# SCH_Syntheseproject2_0_2022-10-21.net
KiCad netlist of a schematic drawn in EasyEDA
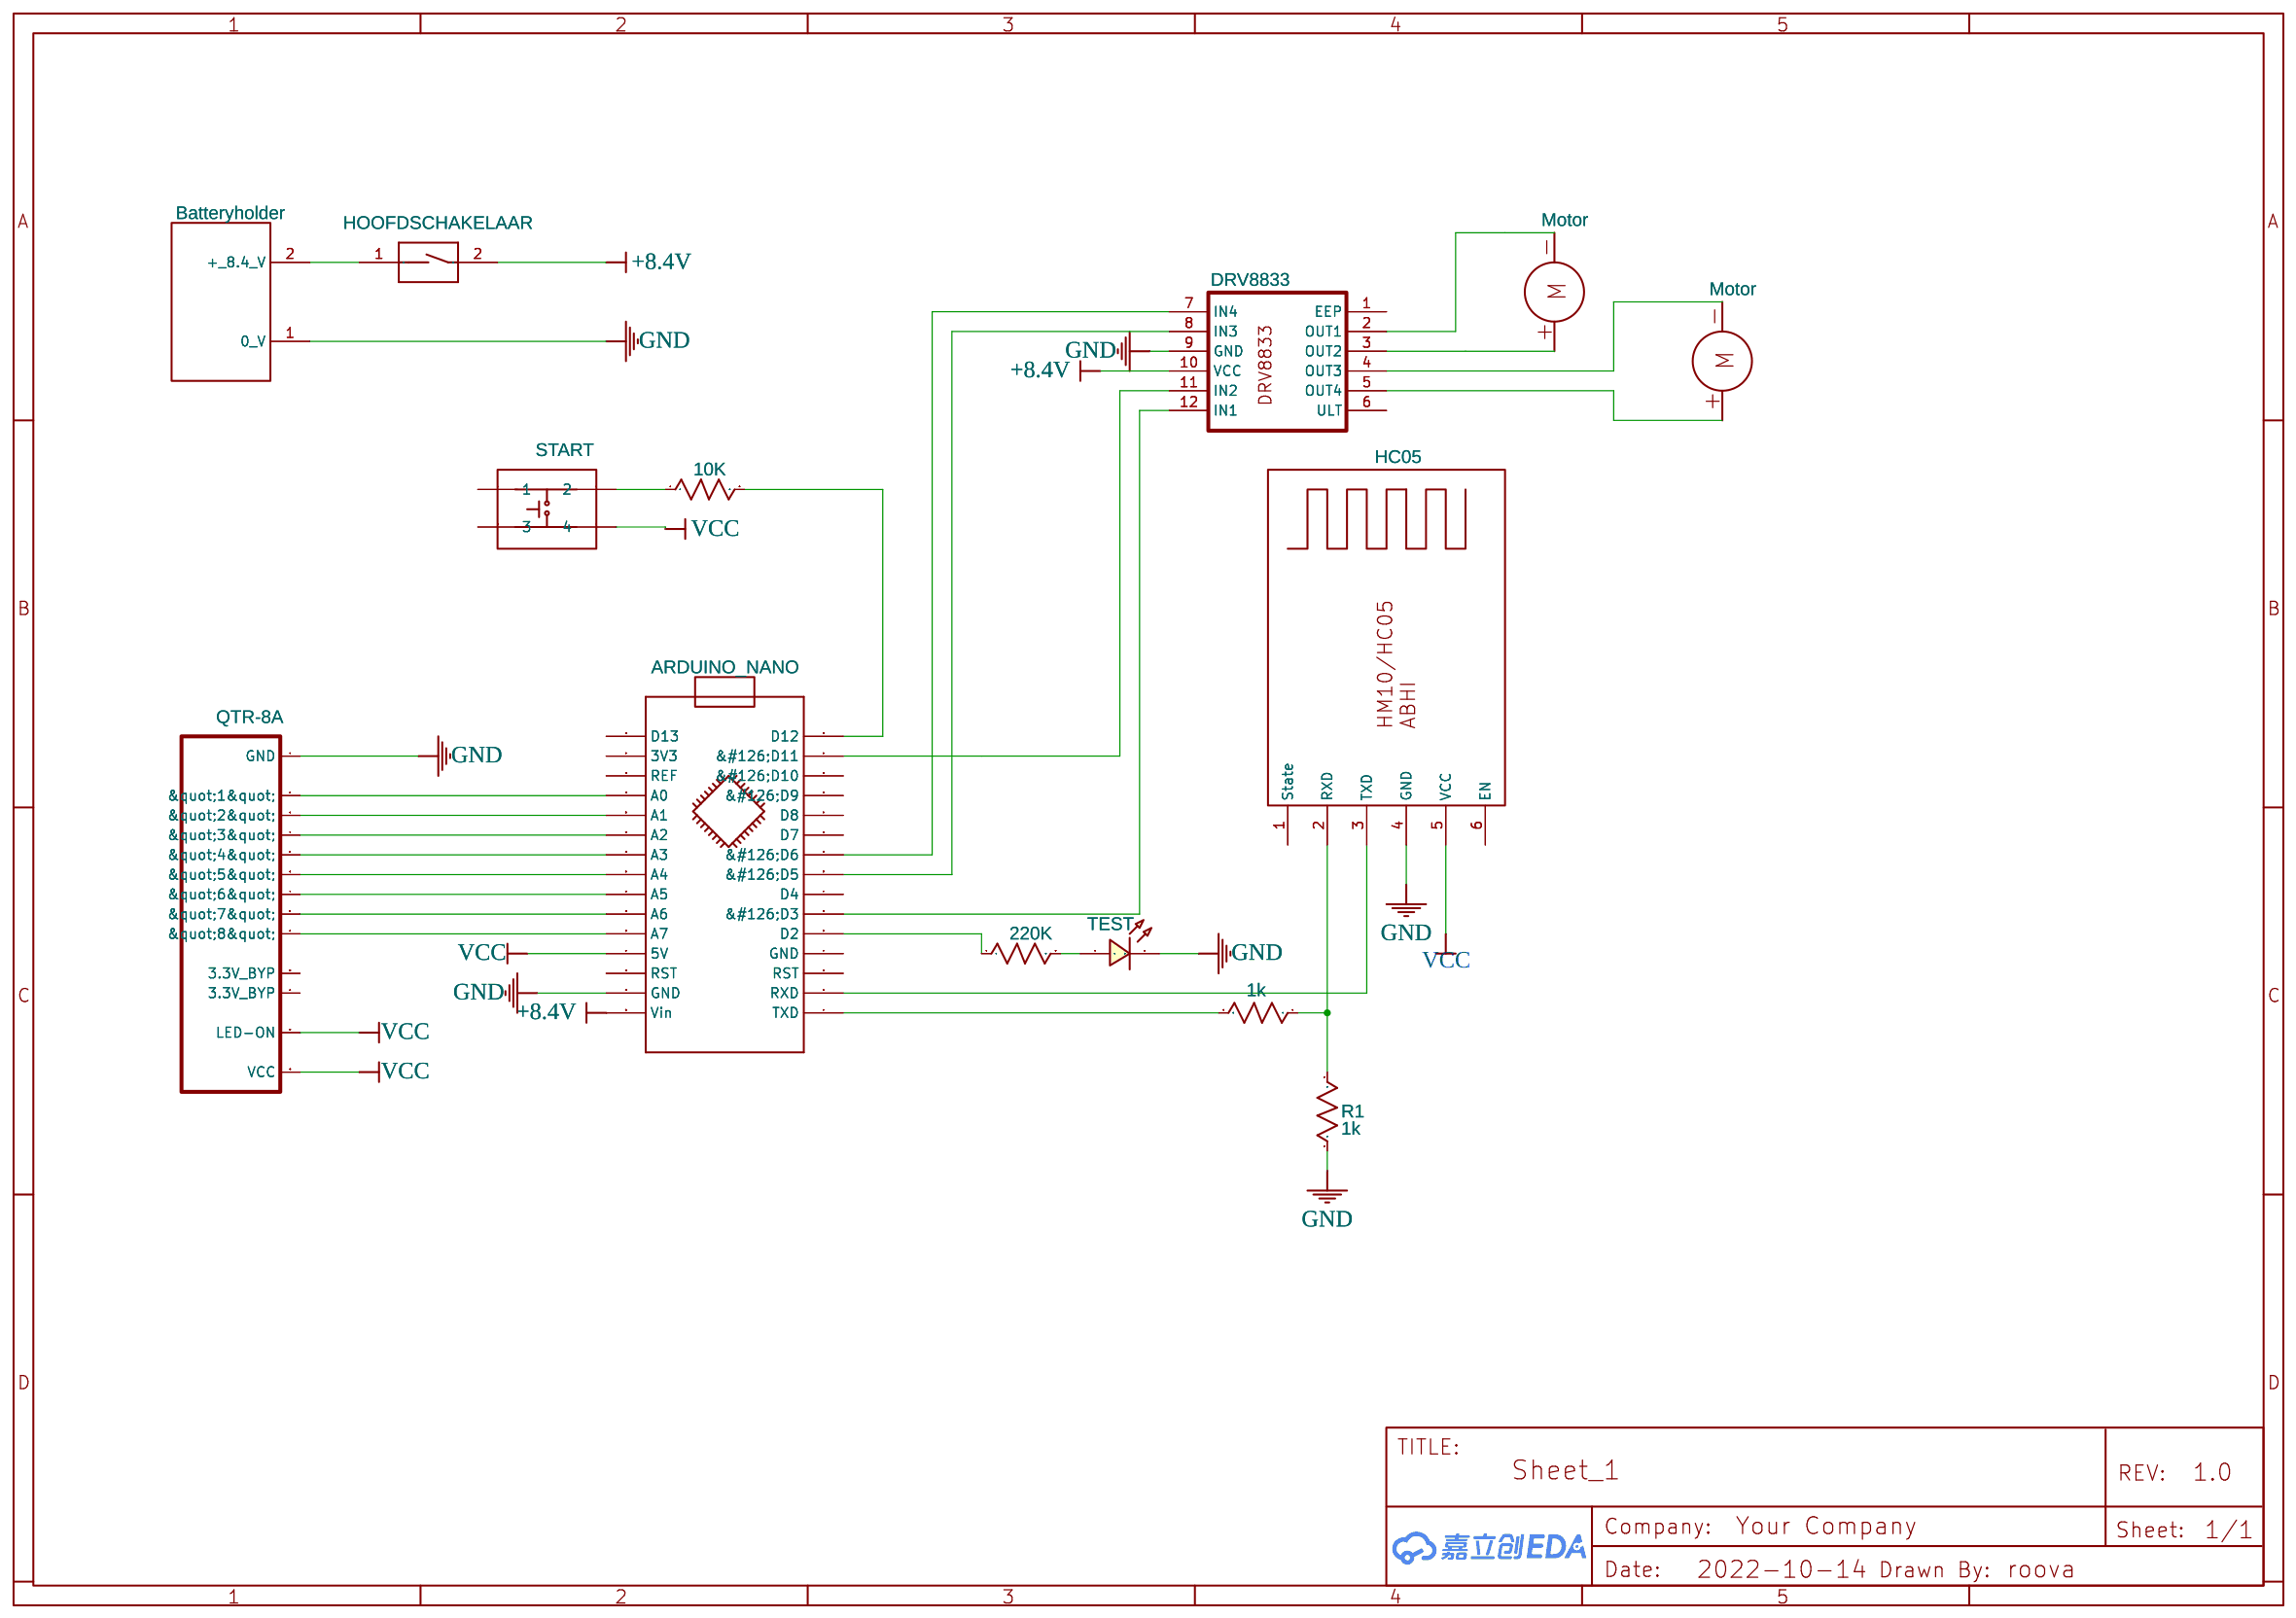
[diagram p0: schematic sheet]

(export (version "E")
  (design (tool "Eeschema 10.0.6"))
  (components
    (comp (ref "10K") (value "1k") (libsource (lib "") (part "R_0603_US_1")))
    (comp (ref "220K") (value "1k") (libsource (lib "") (part "R_0603_US_3")))
    (comp (ref "ARDUINO_NANO")
      (value "ARDUINO-NANO_V3")
      (fields (field (name "BOM_Manufacturer Part") "ARDUINO-NANO_AK"))
      (libsource (lib "") (part "ARDUINO-NANO_V3"))
    )
    (comp (ref "HOOFDSCHAKELAAR")
      (value "DIP1")
      (fields
        (field (name "BOM_Manufacturer Part") "A6TN-1101")
        (field (name "BOM_Supplier Part") "Z12167-ND")
      )
      (libsource (lib "") (part "DIP1"))
    )
    (comp (ref "M2") (value "Motor") (libsource (lib "") (part "Motor")))
    (comp (ref "M3") (value "Motor") (libsource (lib "") (part "Motor")))
    (comp (ref "R1") (value "1k") (libsource (lib "") (part "R_0603_US")))
    (comp (ref "R2") (value "1k") (libsource (lib "") (part "R_0603_US_2")))
    (comp (ref "START")
      (value "PUSHBUTTON 6X6X4.5 4 PINS COPY")
      (fields (field (name "BOM_Manufacturer Part") "sparkfun"))
      (libsource (lib "") (part "PUSHBUTTON 6X6X4.5 4 PINS COPY"))
    )
    (comp (ref "TEST")
      (value "LED-0603_R")
      (fields
        (field (name "BOM_Manufacturer Part") "19-217/R6C-AL1M2VY/3T")
        (field (name "BOM_Supplier Part") "C72044")
      )
      (libsource (lib "") (part "LED-0603_R"))
    )
    (comp (ref "U1") (value "DRV8833") (libsource (lib "") (part "DRV8833 (NO ORIGINAL)")))
    (comp (ref "U2")
      (value "QTR-8A")
      (fields (field (name "BOM_Supplier Part") "960"))
      (libsource (lib "") (part "QTR-8A"))
    )
    (comp (ref "U3") (value "HC05") (libsource (lib "") (part "HC05/HM10-Abhi")))
    (comp (ref "U4") (value "Batteryholder") (libsource (lib "") (part "Batteryholder")))
  )
  (nets
    (net (code "1") (name "+8.4V") (class "Default")
      (node (ref "ARDUINO_NANO") (pin "30") (pinfunction "Vin_30") (pintype "unspecified"))
      (node (ref "HOOFDSCHAKELAAR") (pin "2") (pinfunction "2_2") (pintype "unspecified"))
      (node (ref "U1") (pin "10") (pinfunction "VCC_10") (pintype "unspecified"))
    )
    (net (code "2") (name "GND") (class "Default")
      (node (ref "ARDUINO_NANO") (pin "29") (pinfunction "GND_29") (pintype "unspecified"))
      (node (ref "R1") (pin "1") (pinfunction "1_1") (pintype "unspecified"))
      (node (ref "TEST") (pin "2") (pinfunction "2_2") (pintype "unspecified"))
      (node (ref "U1") (pin "9") (pinfunction "GND_9") (pintype "unspecified"))
      (node (ref "U2") (pin "1") (pinfunction "GND_1") (pintype "unspecified"))
      (node (ref "U3") (pin "4") (pinfunction "GND_4") (pintype "unspecified"))
      (node (ref "U4") (pin "1") (pinfunction "0_V_1") (pintype "unspecified"))
    )
    (net (code "3") (name "Net-(10K-Pad1)") (class "Default")
      (node (ref "10K") (pin "1") (pinfunction "1_1") (pintype "unspecified"))
      (node (ref "START") (pin "2") (pinfunction "2_2") (pintype "unspecified"))
    )
    (net (code "4") (name "Net-(220K-Pad2)") (class "Default")
      (node (ref "220K") (pin "2") (pinfunction "2_2") (pintype "unspecified"))
      (node (ref "TEST") (pin "1") (pinfunction "1_1") (pintype "unspecified"))
    )
    (net (code "5") (name "Net-(ARDUINO_NANO-&#126;D3)") (class "Default")
      (node (ref "ARDUINO_NANO") (pin "6") (pinfunction "&#126;D3_6") (pintype "unspecified"))
      (node (ref "U1") (pin "12") (pinfunction "IN1_12") (pintype "unspecified"))
    )
    (net (code "6") (name "Net-(ARDUINO_NANO-&#126;D5)") (class "Default")
      (node (ref "ARDUINO_NANO") (pin "8") (pinfunction "&#126;D5_8") (pintype "unspecified"))
      (node (ref "U1") (pin "8") (pinfunction "IN3_8") (pintype "unspecified"))
    )
    (net (code "7") (name "Net-(ARDUINO_NANO-&#126;D6)") (class "Default")
      (node (ref "ARDUINO_NANO") (pin "9") (pinfunction "&#126;D6_9") (pintype "unspecified"))
      (node (ref "U1") (pin "7") (pinfunction "IN4_7") (pintype "unspecified"))
    )
    (net (code "8") (name "Net-(ARDUINO_NANO-&#126;D11)") (class "Default")
      (node (ref "ARDUINO_NANO") (pin "14") (pinfunction "&#126;D11_14") (pintype "unspecified"))
      (node (ref "U1") (pin "11") (pinfunction "IN2_11") (pintype "unspecified"))
    )
    (net (code "9") (name "Net-(ARDUINO_NANO-A0)") (class "Default")
      (node (ref "ARDUINO_NANO") (pin "19") (pinfunction "A0_19") (pintype "unspecified"))
      (node (ref "U2") (pin "2") (pinfunction "&quot;1&quot;_2") (pintype "unspecified"))
    )
    (net (code "10") (name "Net-(ARDUINO_NANO-A1)") (class "Default")
      (node (ref "ARDUINO_NANO") (pin "20") (pinfunction "A1_20") (pintype "unspecified"))
      (node (ref "U2") (pin "3") (pinfunction "&quot;2&quot;_3") (pintype "unspecified"))
    )
    (net (code "11") (name "Net-(ARDUINO_NANO-A2)") (class "Default")
      (node (ref "ARDUINO_NANO") (pin "21") (pinfunction "A2_21") (pintype "unspecified"))
      (node (ref "U2") (pin "4") (pinfunction "&quot;3&quot;_4") (pintype "unspecified"))
    )
    (net (code "12") (name "Net-(ARDUINO_NANO-A3)") (class "Default")
      (node (ref "ARDUINO_NANO") (pin "22") (pinfunction "A3_22") (pintype "unspecified"))
      (node (ref "U2") (pin "5") (pinfunction "&quot;4&quot;_5") (pintype "unspecified"))
    )
    (net (code "13") (name "Net-(ARDUINO_NANO-A4)") (class "Default")
      (node (ref "ARDUINO_NANO") (pin "23") (pinfunction "A4_23") (pintype "unspecified"))
      (node (ref "U2") (pin "6") (pinfunction "&quot;5&quot;_6") (pintype "unspecified"))
    )
    (net (code "14") (name "Net-(ARDUINO_NANO-A5)") (class "Default")
      (node (ref "ARDUINO_NANO") (pin "24") (pinfunction "A5_24") (pintype "unspecified"))
      (node (ref "U2") (pin "7") (pinfunction "&quot;6&quot;_7") (pintype "unspecified"))
    )
    (net (code "15") (name "Net-(ARDUINO_NANO-A6)") (class "Default")
      (node (ref "ARDUINO_NANO") (pin "25") (pinfunction "A6_25") (pintype "unspecified"))
      (node (ref "U2") (pin "8") (pinfunction "&quot;7&quot;_8") (pintype "unspecified"))
    )
    (net (code "16") (name "Net-(ARDUINO_NANO-A7)") (class "Default")
      (node (ref "ARDUINO_NANO") (pin "26") (pinfunction "A7_26") (pintype "unspecified"))
      (node (ref "U2") (pin "9") (pinfunction "&quot;8&quot;_9") (pintype "unspecified"))
    )
    (net (code "17") (name "Net-(ARDUINO_NANO-D2)") (class "Default")
      (node (ref "220K") (pin "1") (pinfunction "1_1") (pintype "unspecified"))
      (node (ref "ARDUINO_NANO") (pin "5") (pinfunction "D2_5") (pintype "unspecified"))
    )
    (net (code "18") (name "Net-(ARDUINO_NANO-D12)") (class "Default")
      (node (ref "10K") (pin "2") (pinfunction "2_2") (pintype "unspecified"))
      (node (ref "ARDUINO_NANO") (pin "15") (pinfunction "D12_15") (pintype "unspecified"))
    )
    (net (code "19") (name "Net-(ARDUINO_NANO-RXD)") (class "Default")
      (node (ref "ARDUINO_NANO") (pin "2") (pinfunction "RXD_2") (pintype "unspecified"))
      (node (ref "U3") (pin "3") (pinfunction "TXD_3") (pintype "unspecified"))
    )
    (net (code "20") (name "Net-(ARDUINO_NANO-TXD)") (class "Default")
      (node (ref "ARDUINO_NANO") (pin "1") (pinfunction "TXD_1") (pintype "unspecified"))
      (node (ref "R2") (pin "2") (pinfunction "2_2") (pintype "unspecified"))
    )
    (net (code "21") (name "Net-(U3-RXD)") (class "Default")
      (node (ref "R1") (pin "2") (pinfunction "2_2") (pintype "unspecified"))
      (node (ref "R2") (pin "1") (pinfunction "1_1") (pintype "unspecified"))
      (node (ref "U3") (pin "2") (pinfunction "RXD_2") (pintype "unspecified"))
    )
    (net (code "22") (name "Net-(U4-+_8.4_V)") (class "Default")
      (node (ref "HOOFDSCHAKELAAR") (pin "1") (pinfunction "1_1") (pintype "unspecified"))
      (node (ref "U4") (pin "2") (pinfunction "+_8.4_V_2") (pintype "unspecified"))
    )
    (net (code "23") (name "VCC") (class "Default")
      (node (ref "ARDUINO_NANO") (pin "27") (pinfunction "5V_27") (pintype "unspecified"))
      (node (ref "START") (pin "4") (pinfunction "4_4") (pintype "unspecified"))
      (node (ref "U2") (pin "12") (pinfunction "LED-ON_12") (pintype "unspecified"))
      (node (ref "U3") (pin "5") (pinfunction "VCC_5") (pintype "unspecified"))
    )
    (net (code "24") (name "unconnected-(ARDUINO_NANO-&#126;D9-Pad12)") (class "Default")
      (node (ref "ARDUINO_NANO") (pin "12") (pinfunction "&#126;D9_12") (pintype "unspecified"))
    )
    (net (code "25") (name "unconnected-(ARDUINO_NANO-&#126;D10-Pad13)") (class "Default")
      (node (ref "ARDUINO_NANO") (pin "13") (pinfunction "&#126;D10_13") (pintype "unspecified"))
    )
    (net (code "26") (name "unconnected-(ARDUINO_NANO-3V3-Pad17)") (class "Default")
      (node (ref "ARDUINO_NANO") (pin "17") (pinfunction "3V3_17") (pintype "unspecified"))
    )
    (net (code "27") (name "unconnected-(ARDUINO_NANO-D4-Pad7)") (class "Default")
      (node (ref "ARDUINO_NANO") (pin "7") (pinfunction "D4_7") (pintype "unspecified"))
    )
    (net (code "28") (name "unconnected-(ARDUINO_NANO-D7-Pad10)") (class "Default")
      (node (ref "ARDUINO_NANO") (pin "10") (pinfunction "D7_10") (pintype "unspecified"))
    )
    (net (code "29") (name "unconnected-(ARDUINO_NANO-D8-Pad11)") (class "Default")
      (node (ref "ARDUINO_NANO") (pin "11") (pinfunction "D8_11") (pintype "unspecified"))
    )
    (net (code "30") (name "unconnected-(ARDUINO_NANO-D13-Pad16)") (class "Default")
      (node (ref "ARDUINO_NANO") (pin "16") (pinfunction "D13_16") (pintype "unspecified"))
    )
    (net (code "31") (name "unconnected-(ARDUINO_NANO-GND-Pad4)") (class "Default")
      (node (ref "ARDUINO_NANO") (pin "4") (pinfunction "GND_4") (pintype "unspecified"))
    )
    (net (code "32") (name "unconnected-(ARDUINO_NANO-REF-Pad18)") (class "Default")
      (node (ref "ARDUINO_NANO") (pin "18") (pinfunction "REF_18") (pintype "unspecified"))
    )
    (net (code "33") (name "unconnected-(ARDUINO_NANO-RST-Pad3)") (class "Default")
      (node (ref "ARDUINO_NANO") (pin "3") (pinfunction "RST_3") (pintype "unspecified"))
    )
    (net (code "34") (name "unconnected-(ARDUINO_NANO-RST-Pad28)") (class "Default")
      (node (ref "ARDUINO_NANO") (pin "28") (pinfunction "RST_28") (pintype "unspecified"))
    )
    (net (code "35") (name "unconnected-(START-Pad1)") (class "Default")
      (node (ref "START") (pin "1") (pinfunction "1_1") (pintype "unspecified"))
    )
    (net (code "36") (name "unconnected-(START-Pad3)") (class "Default")
      (node (ref "START") (pin "3") (pinfunction "3_3") (pintype "unspecified"))
    )
    (net (code "37") (name "unconnected-(U1-EEP-Pad1)") (class "Default")
      (node (ref "U1") (pin "1") (pinfunction "EEP_1") (pintype "unspecified"))
    )
    (net (code "38") (name "unconnected-(U1-OUT1-Pad2)") (class "Default")
      (node (ref "U1") (pin "2") (pinfunction "OUT1_2") (pintype "unspecified"))
    )
    (net (code "39") (name "unconnected-(U1-OUT2-Pad3)") (class "Default")
      (node (ref "U1") (pin "3") (pinfunction "OUT2_3") (pintype "unspecified"))
    )
    (net (code "40") (name "unconnected-(U1-OUT3-Pad4)") (class "Default")
      (node (ref "U1") (pin "4") (pinfunction "OUT3_4") (pintype "unspecified"))
    )
    (net (code "41") (name "unconnected-(U1-OUT4-Pad5)") (class "Default")
      (node (ref "U1") (pin "5") (pinfunction "OUT4_5") (pintype "unspecified"))
    )
    (net (code "42") (name "unconnected-(U1-ULT-Pad6)") (class "Default")
      (node (ref "U1") (pin "6") (pinfunction "ULT_6") (pintype "unspecified"))
    )
    (net (code "43") (name "unconnected-(U2-3.3V_BYP-Pad10)") (class "Default")
      (node (ref "U2") (pin "10") (pinfunction "3.3V_BYP_10") (pintype "unspecified"))
    )
    (net (code "44") (name "unconnected-(U2-3.3V_BYP-Pad11)") (class "Default")
      (node (ref "U2") (pin "11") (pinfunction "3.3V_BYP_11") (pintype "unspecified"))
    )
    (net (code "45") (name "unconnected-(U3-EN-Pad6)") (class "Default")
      (node (ref "U3") (pin "6") (pinfunction "EN_6") (pintype "unspecified"))
    )
    (net (code "46") (name "unconnected-(U3-State-Pad1)") (class "Default")
      (node (ref "U3") (pin "1") (pinfunction "State_1") (pintype "unspecified"))
    )
  )
)
